# Schematic.net
KiCad netlist of a schematic drawn in Altium Designer
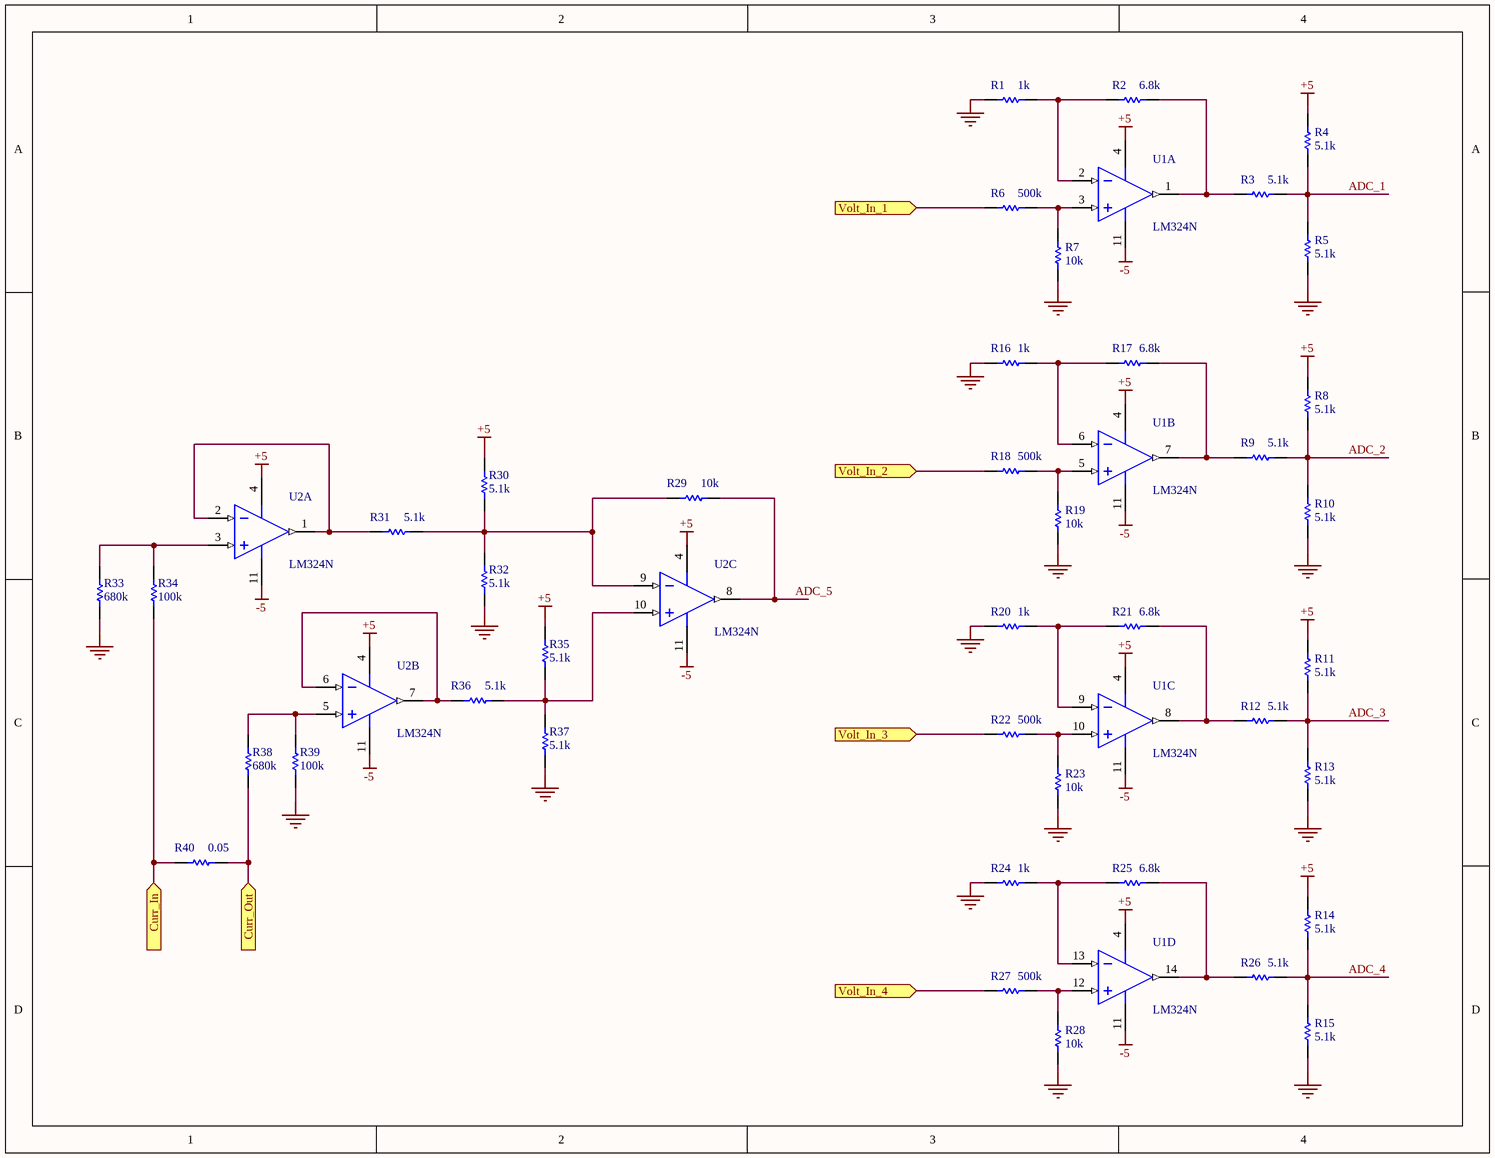
[diagram p0: Schematic.SchDoc]

(export (version "E")
  (design (tool "Eeschema 10.0.6"))
  (components
    (comp (ref "R1")
      (value "1k")
      (footprint "AXIAL-0.3")
      (description "Resistor")
      (fields (field (name "PUBLISHER") "Altium Limited"))
      (libsource (lib "Miscellaneous Devices") (part "Res1"))
    )
    (comp (ref "R2")
      (value "6.8k")
      (footprint "AXIAL-0.3")
      (description "Resistor")
      (fields (field (name "PUBLISHER") "Altium Limited"))
      (libsource (lib "Miscellaneous Devices") (part "Res1"))
    )
    (comp (ref "R3")
      (value "5.1k")
      (footprint "AXIAL-0.3")
      (description "Resistor")
      (fields (field (name "PUBLISHER") "Altium Limited"))
      (libsource (lib "Miscellaneous Devices") (part "Res1"))
    )
    (comp (ref "R4")
      (value "5.1k")
      (footprint "AXIAL-0.3")
      (description "Resistor")
      (fields (field (name "PUBLISHER") "Altium Limited"))
      (libsource (lib "Miscellaneous Devices") (part "Res1"))
    )
    (comp (ref "R5")
      (value "5.1k")
      (footprint "AXIAL-0.3")
      (description "Resistor")
      (fields (field (name "PUBLISHER") "Altium Limited"))
      (libsource (lib "Miscellaneous Devices") (part "Res1"))
    )
    (comp (ref "R6")
      (value "500k")
      (footprint "AXIAL-0.3")
      (description "Resistor")
      (fields (field (name "PUBLISHER") "Altium Limited"))
      (libsource (lib "Miscellaneous Devices") (part "Res1"))
    )
    (comp (ref "R7")
      (value "10k")
      (footprint "AXIAL-0.3")
      (description "Resistor")
      (fields (field (name "PUBLISHER") "Altium Limited"))
      (libsource (lib "Miscellaneous Devices") (part "Res1"))
    )
    (comp (ref "R8")
      (value "5.1k")
      (footprint "AXIAL-0.3")
      (description "Resistor")
      (fields (field (name "PUBLISHER") "Altium Limited"))
      (libsource (lib "Miscellaneous Devices") (part "Res1"))
    )
    (comp (ref "R9")
      (value "5.1k")
      (footprint "AXIAL-0.3")
      (description "Resistor")
      (fields (field (name "PUBLISHER") "Altium Limited"))
      (libsource (lib "Miscellaneous Devices") (part "Res1"))
    )
    (comp (ref "R10")
      (value "5.1k")
      (footprint "AXIAL-0.3")
      (description "Resistor")
      (fields (field (name "PUBLISHER") "Altium Limited"))
      (libsource (lib "Miscellaneous Devices") (part "Res1"))
    )
    (comp (ref "R11")
      (value "5.1k")
      (footprint "AXIAL-0.3")
      (description "Resistor")
      (fields (field (name "PUBLISHER") "Altium Limited"))
      (libsource (lib "Miscellaneous Devices") (part "Res1"))
    )
    (comp (ref "R12")
      (value "5.1k")
      (footprint "AXIAL-0.3")
      (description "Resistor")
      (fields (field (name "PUBLISHER") "Altium Limited"))
      (libsource (lib "Miscellaneous Devices") (part "Res1"))
    )
    (comp (ref "R13")
      (value "5.1k")
      (footprint "AXIAL-0.3")
      (description "Resistor")
      (fields (field (name "PUBLISHER") "Altium Limited"))
      (libsource (lib "Miscellaneous Devices") (part "Res1"))
    )
    (comp (ref "R14")
      (value "5.1k")
      (footprint "AXIAL-0.3")
      (description "Resistor")
      (fields (field (name "PUBLISHER") "Altium Limited"))
      (libsource (lib "Miscellaneous Devices") (part "Res1"))
    )
    (comp (ref "R15")
      (value "5.1k")
      (footprint "AXIAL-0.3")
      (description "Resistor")
      (fields (field (name "PUBLISHER") "Altium Limited"))
      (libsource (lib "Miscellaneous Devices") (part "Res1"))
    )
    (comp (ref "R16")
      (value "1k")
      (footprint "AXIAL-0.3")
      (description "Resistor")
      (fields (field (name "PUBLISHER") "Altium Limited"))
      (libsource (lib "Miscellaneous Devices") (part "Res1"))
    )
    (comp (ref "R17")
      (value "6.8k")
      (footprint "AXIAL-0.3")
      (description "Resistor")
      (fields (field (name "PUBLISHER") "Altium Limited"))
      (libsource (lib "Miscellaneous Devices") (part "Res1"))
    )
    (comp (ref "R18")
      (value "500k")
      (footprint "AXIAL-0.3")
      (description "Resistor")
      (fields (field (name "PUBLISHER") "Altium Limited"))
      (libsource (lib "Miscellaneous Devices") (part "Res1"))
    )
    (comp (ref "R19")
      (value "10k")
      (footprint "AXIAL-0.3")
      (description "Resistor")
      (fields (field (name "PUBLISHER") "Altium Limited"))
      (libsource (lib "Miscellaneous Devices") (part "Res1"))
    )
    (comp (ref "R20")
      (value "1k")
      (footprint "AXIAL-0.3")
      (description "Resistor")
      (fields (field (name "PUBLISHER") "Altium Limited"))
      (libsource (lib "Miscellaneous Devices") (part "Res1"))
    )
    (comp (ref "R21")
      (value "6.8k")
      (footprint "AXIAL-0.3")
      (description "Resistor")
      (fields (field (name "PUBLISHER") "Altium Limited"))
      (libsource (lib "Miscellaneous Devices") (part "Res1"))
    )
    (comp (ref "R22")
      (value "500k")
      (footprint "AXIAL-0.3")
      (description "Resistor")
      (fields (field (name "PUBLISHER") "Altium Limited"))
      (libsource (lib "Miscellaneous Devices") (part "Res1"))
    )
    (comp (ref "R23")
      (value "10k")
      (footprint "AXIAL-0.3")
      (description "Resistor")
      (fields (field (name "PUBLISHER") "Altium Limited"))
      (libsource (lib "Miscellaneous Devices") (part "Res1"))
    )
    (comp (ref "R24")
      (value "1k")
      (footprint "AXIAL-0.3")
      (description "Resistor")
      (fields (field (name "PUBLISHER") "Altium Limited"))
      (libsource (lib "Miscellaneous Devices") (part "Res1"))
    )
    (comp (ref "R25")
      (value "6.8k")
      (footprint "AXIAL-0.3")
      (description "Resistor")
      (fields (field (name "PUBLISHER") "Altium Limited"))
      (libsource (lib "Miscellaneous Devices") (part "Res1"))
    )
    (comp (ref "R26")
      (value "5.1k")
      (footprint "AXIAL-0.3")
      (description "Resistor")
      (fields (field (name "PUBLISHER") "Altium Limited"))
      (libsource (lib "Miscellaneous Devices") (part "Res1"))
    )
    (comp (ref "R27")
      (value "500k")
      (footprint "AXIAL-0.3")
      (description "Resistor")
      (fields (field (name "PUBLISHER") "Altium Limited"))
      (libsource (lib "Miscellaneous Devices") (part "Res1"))
    )
    (comp (ref "R28")
      (value "10k")
      (footprint "AXIAL-0.3")
      (description "Resistor")
      (fields (field (name "PUBLISHER") "Altium Limited"))
      (libsource (lib "Miscellaneous Devices") (part "Res1"))
    )
    (comp (ref "R29")
      (value "10k")
      (footprint "AXIAL-0.3")
      (description "Resistor")
      (fields (field (name "PUBLISHER") "Altium Limited"))
      (libsource (lib "Miscellaneous Devices") (part "Res1"))
    )
    (comp (ref "R30")
      (value "5.1k")
      (footprint "AXIAL-0.3")
      (description "Resistor")
      (fields (field (name "PUBLISHER") "Altium Limited"))
      (libsource (lib "Miscellaneous Devices") (part "Res1"))
    )
    (comp (ref "R31")
      (value "5.1k")
      (footprint "AXIAL-0.3")
      (description "Resistor")
      (fields (field (name "PUBLISHER") "Altium Limited"))
      (libsource (lib "Miscellaneous Devices") (part "Res1"))
    )
    (comp (ref "R32")
      (value "5.1k")
      (footprint "AXIAL-0.3")
      (description "Resistor")
      (fields (field (name "PUBLISHER") "Altium Limited"))
      (libsource (lib "Miscellaneous Devices") (part "Res1"))
    )
    (comp (ref "R33")
      (value "680k")
      (footprint "AXIAL-0.3")
      (description "Resistor")
      (fields (field (name "PUBLISHER") "Altium Limited"))
      (libsource (lib "Miscellaneous Devices") (part "Res1"))
    )
    (comp (ref "R34")
      (value "100k")
      (footprint "AXIAL-0.3")
      (description "Resistor")
      (fields (field (name "PUBLISHER") "Altium Limited"))
      (libsource (lib "Miscellaneous Devices") (part "Res1"))
    )
    (comp (ref "R35")
      (value "5.1k")
      (footprint "AXIAL-0.3")
      (description "Resistor")
      (fields (field (name "PUBLISHER") "Altium Limited"))
      (libsource (lib "Miscellaneous Devices") (part "Res1"))
    )
    (comp (ref "R36")
      (value "5.1k")
      (footprint "AXIAL-0.3")
      (description "Resistor")
      (fields (field (name "PUBLISHER") "Altium Limited"))
      (libsource (lib "Miscellaneous Devices") (part "Res1"))
    )
    (comp (ref "R37")
      (value "5.1k")
      (footprint "AXIAL-0.3")
      (description "Resistor")
      (fields (field (name "PUBLISHER") "Altium Limited"))
      (libsource (lib "Miscellaneous Devices") (part "Res1"))
    )
    (comp (ref "R38")
      (value "680k")
      (footprint "AXIAL-0.3")
      (description "Resistor")
      (fields (field (name "PUBLISHER") "Altium Limited"))
      (libsource (lib "Miscellaneous Devices") (part "Res1"))
    )
    (comp (ref "R39")
      (value "100k")
      (footprint "AXIAL-0.3")
      (description "Resistor")
      (fields (field (name "PUBLISHER") "Altium Limited"))
      (libsource (lib "Miscellaneous Devices") (part "Res1"))
    )
    (comp (ref "R40")
      (value "0.05")
      (footprint "AXIAL-0.3")
      (description "Resistor")
      (fields (field (name "PUBLISHER") "Altium Limited"))
      (libsource (lib "Miscellaneous Devices") (part "Res1"))
    )
    (comp (ref "U1")
      (value "LM324N")
      (footprint "N0014A")
      (description "Low Power Quad Operational Amplifier, 14-pin MDIP")
      (fields (field (name "MANUFACTURER") "Texas Instruments"))
      (libsource (lib "Altium Content Vault") (part "AMP-OPA-LM124-14"))
    )
    (comp (ref "U2")
      (value "LM324N")
      (footprint "N0014A")
      (description "Low Power Quad Operational Amplifier, 14-pin MDIP")
      (fields (field (name "MANUFACTURER") "Texas Instruments"))
      (libsource (lib "Altium Content Vault") (part "AMP-OPA-LM124-14"))
    )
  )
  (nets
    (net (code "1") (name "+5") (class "Default")
      (node (ref "R11") (pin "2") (pinfunction "2_2") (pintype "passive"))
      (node (ref "R14") (pin "2") (pinfunction "2_2") (pintype "passive"))
      (node (ref "R30") (pin "2") (pinfunction "2_2") (pintype "passive"))
      (node (ref "R35") (pin "2") (pinfunction "2_2") (pintype "passive"))
      (node (ref "R4") (pin "2") (pinfunction "2_2") (pintype "passive"))
      (node (ref "R8") (pin "2") (pinfunction "2_2") (pintype "passive"))
      (node (ref "U1") (pin "4") (pinfunction "V+_4") (pintype "power_in"))
      (node (ref "U2") (pin "4") (pinfunction "V+_4") (pintype "power_in"))
    )
    (net (code "2") (name "-5") (class "Default")
      (node (ref "U1") (pin "11") (pinfunction "GND_11") (pintype "power_in"))
      (node (ref "U2") (pin "11") (pinfunction "GND_11") (pintype "power_in"))
    )
    (net (code "3") (name "/ADC_1") (class "Default")
      (node (ref "R3") (pin "2") (pinfunction "2_2") (pintype "passive"))
      (node (ref "R4") (pin "1") (pinfunction "1_1") (pintype "passive"))
      (node (ref "R5") (pin "2") (pinfunction "2_2") (pintype "passive"))
    )
    (net (code "4") (name "/ADC_2") (class "Default")
      (node (ref "R10") (pin "2") (pinfunction "2_2") (pintype "passive"))
      (node (ref "R8") (pin "1") (pinfunction "1_1") (pintype "passive"))
      (node (ref "R9") (pin "2") (pinfunction "2_2") (pintype "passive"))
    )
    (net (code "5") (name "/ADC_3") (class "Default")
      (node (ref "R11") (pin "1") (pinfunction "1_1") (pintype "passive"))
      (node (ref "R12") (pin "2") (pinfunction "2_2") (pintype "passive"))
      (node (ref "R13") (pin "2") (pinfunction "2_2") (pintype "passive"))
    )
    (net (code "6") (name "/ADC_4") (class "Default")
      (node (ref "R14") (pin "1") (pinfunction "1_1") (pintype "passive"))
      (node (ref "R15") (pin "2") (pinfunction "2_2") (pintype "passive"))
      (node (ref "R26") (pin "2") (pinfunction "2_2") (pintype "passive"))
    )
    (net (code "7") (name "/ADC_5") (class "Default")
      (node (ref "R29") (pin "1") (pinfunction "1_1") (pintype "passive"))
      (node (ref "U2") (pin "8") (pinfunction "OUT3_8") (pintype "output"))
    )
    (net (code "8") (name "/Curr_In") (class "Default")
      (node (ref "R34") (pin "1") (pinfunction "1_1") (pintype "passive"))
      (node (ref "R40") (pin "1") (pinfunction "1_1") (pintype "passive"))
    )
    (net (code "9") (name "/Curr_Out") (class "Default")
      (node (ref "R38") (pin "1") (pinfunction "1_1") (pintype "passive"))
      (node (ref "R40") (pin "2") (pinfunction "2_2") (pintype "passive"))
    )
    (net (code "10") (name "/Volt_In_1") (class "Default")
      (node (ref "R6") (pin "1") (pinfunction "1_1") (pintype "passive"))
    )
    (net (code "11") (name "/Volt_In_2") (class "Default")
      (node (ref "R18") (pin "1") (pinfunction "1_1") (pintype "passive"))
    )
    (net (code "12") (name "/Volt_In_3") (class "Default")
      (node (ref "R22") (pin "1") (pinfunction "1_1") (pintype "passive"))
    )
    (net (code "13") (name "/Volt_In_4") (class "Default")
      (node (ref "R27") (pin "1") (pinfunction "1_1") (pintype "passive"))
    )
    (net (code "14") (name "GND") (class "Default")
      (node (ref "R1") (pin "1") (pinfunction "1_1") (pintype "passive"))
      (node (ref "R10") (pin "1") (pinfunction "1_1") (pintype "passive"))
      (node (ref "R13") (pin "1") (pinfunction "1_1") (pintype "passive"))
      (node (ref "R15") (pin "1") (pinfunction "1_1") (pintype "passive"))
      (node (ref "R16") (pin "1") (pinfunction "1_1") (pintype "passive"))
      (node (ref "R19") (pin "1") (pinfunction "1_1") (pintype "passive"))
      (node (ref "R20") (pin "1") (pinfunction "1_1") (pintype "passive"))
      (node (ref "R23") (pin "1") (pinfunction "1_1") (pintype "passive"))
      (node (ref "R24") (pin "1") (pinfunction "1_1") (pintype "passive"))
      (node (ref "R28") (pin "1") (pinfunction "1_1") (pintype "passive"))
      (node (ref "R32") (pin "1") (pinfunction "1_1") (pintype "passive"))
      (node (ref "R33") (pin "1") (pinfunction "1_1") (pintype "passive"))
      (node (ref "R37") (pin "1") (pinfunction "1_1") (pintype "passive"))
      (node (ref "R39") (pin "1") (pinfunction "1_1") (pintype "passive"))
      (node (ref "R5") (pin "1") (pinfunction "1_1") (pintype "passive"))
      (node (ref "R7") (pin "1") (pinfunction "1_1") (pintype "passive"))
    )
    (net (code "15") (name "Net-(U1A-IN1+)") (class "Default")
      (node (ref "R6") (pin "2") (pinfunction "2_2") (pintype "passive"))
      (node (ref "R7") (pin "2") (pinfunction "2_2") (pintype "passive"))
      (node (ref "U1") (pin "3") (pinfunction "IN1+_3") (pintype "input"))
    )
    (net (code "16") (name "Net-(U1A-IN1-)") (class "Default")
      (node (ref "R1") (pin "2") (pinfunction "2_2") (pintype "passive"))
      (node (ref "R2") (pin "1") (pinfunction "1_1") (pintype "passive"))
      (node (ref "U1") (pin "2") (pinfunction "IN1-_2") (pintype "input"))
    )
    (net (code "17") (name "Net-(U1A-OUT1)") (class "Default")
      (node (ref "R2") (pin "2") (pinfunction "2_2") (pintype "passive"))
      (node (ref "R3") (pin "1") (pinfunction "1_1") (pintype "passive"))
      (node (ref "U1") (pin "1") (pinfunction "OUT1_1") (pintype "output"))
    )
    (net (code "18") (name "Net-(U1B-IN2+)") (class "Default")
      (node (ref "R18") (pin "2") (pinfunction "2_2") (pintype "passive"))
      (node (ref "R19") (pin "2") (pinfunction "2_2") (pintype "passive"))
      (node (ref "U1") (pin "5") (pinfunction "IN2+_5") (pintype "input"))
    )
    (net (code "19") (name "Net-(U1B-IN2-)") (class "Default")
      (node (ref "R16") (pin "2") (pinfunction "2_2") (pintype "passive"))
      (node (ref "R17") (pin "1") (pinfunction "1_1") (pintype "passive"))
      (node (ref "U1") (pin "6") (pinfunction "IN2-_6") (pintype "input"))
    )
    (net (code "20") (name "Net-(U1B-OUT2)") (class "Default")
      (node (ref "R17") (pin "2") (pinfunction "2_2") (pintype "passive"))
      (node (ref "R9") (pin "1") (pinfunction "1_1") (pintype "passive"))
      (node (ref "U1") (pin "7") (pinfunction "OUT2_7") (pintype "output"))
    )
    (net (code "21") (name "Net-(U1C-IN3+)") (class "Default")
      (node (ref "R22") (pin "2") (pinfunction "2_2") (pintype "passive"))
      (node (ref "R23") (pin "2") (pinfunction "2_2") (pintype "passive"))
      (node (ref "U1") (pin "10") (pinfunction "IN3+_10") (pintype "input"))
    )
    (net (code "22") (name "Net-(U1C-IN3-)") (class "Default")
      (node (ref "R20") (pin "2") (pinfunction "2_2") (pintype "passive"))
      (node (ref "R21") (pin "1") (pinfunction "1_1") (pintype "passive"))
      (node (ref "U1") (pin "9") (pinfunction "IN3-_9") (pintype "input"))
    )
    (net (code "23") (name "Net-(U1C-OUT3)") (class "Default")
      (node (ref "R12") (pin "1") (pinfunction "1_1") (pintype "passive"))
      (node (ref "R21") (pin "2") (pinfunction "2_2") (pintype "passive"))
      (node (ref "U1") (pin "8") (pinfunction "OUT3_8") (pintype "output"))
    )
    (net (code "24") (name "Net-(U1D-IN4+)") (class "Default")
      (node (ref "R27") (pin "2") (pinfunction "2_2") (pintype "passive"))
      (node (ref "R28") (pin "2") (pinfunction "2_2") (pintype "passive"))
      (node (ref "U1") (pin "12") (pinfunction "IN4+_12") (pintype "input"))
    )
    (net (code "25") (name "Net-(U1D-IN4-)") (class "Default")
      (node (ref "R24") (pin "2") (pinfunction "2_2") (pintype "passive"))
      (node (ref "R25") (pin "1") (pinfunction "1_1") (pintype "passive"))
      (node (ref "U1") (pin "13") (pinfunction "IN4-_13") (pintype "input"))
    )
    (net (code "26") (name "Net-(U1D-OUT4)") (class "Default")
      (node (ref "R25") (pin "2") (pinfunction "2_2") (pintype "passive"))
      (node (ref "R26") (pin "1") (pinfunction "1_1") (pintype "passive"))
      (node (ref "U1") (pin "14") (pinfunction "OUT4_14") (pintype "output"))
    )
    (net (code "27") (name "Net-(U2A-IN1+)") (class "Default")
      (node (ref "R33") (pin "2") (pinfunction "2_2") (pintype "passive"))
      (node (ref "R34") (pin "2") (pinfunction "2_2") (pintype "passive"))
      (node (ref "U2") (pin "3") (pinfunction "IN1+_3") (pintype "input"))
    )
    (net (code "28") (name "Net-(U2A-IN1-)") (class "Default")
      (node (ref "R31") (pin "2") (pinfunction "2_2") (pintype "passive"))
      (node (ref "U2") (pin "1") (pinfunction "OUT1_1") (pintype "output"))
      (node (ref "U2") (pin "2") (pinfunction "IN1-_2") (pintype "input"))
    )
    (net (code "29") (name "Net-(U2B-IN2+)") (class "Default")
      (node (ref "R38") (pin "2") (pinfunction "2_2") (pintype "passive"))
      (node (ref "R39") (pin "2") (pinfunction "2_2") (pintype "passive"))
      (node (ref "U2") (pin "5") (pinfunction "IN2+_5") (pintype "input"))
    )
    (net (code "30") (name "Net-(U2B-IN2-)") (class "Default")
      (node (ref "R36") (pin "2") (pinfunction "2_2") (pintype "passive"))
      (node (ref "U2") (pin "6") (pinfunction "IN2-_6") (pintype "input"))
      (node (ref "U2") (pin "7") (pinfunction "OUT2_7") (pintype "output"))
    )
    (net (code "31") (name "Net-(U2C-IN3+)") (class "Default")
      (node (ref "R35") (pin "1") (pinfunction "1_1") (pintype "passive"))
      (node (ref "R36") (pin "1") (pinfunction "1_1") (pintype "passive"))
      (node (ref "R37") (pin "2") (pinfunction "2_2") (pintype "passive"))
      (node (ref "U2") (pin "10") (pinfunction "IN3+_10") (pintype "input"))
    )
    (net (code "32") (name "Net-(U2C-IN3-)") (class "Default")
      (node (ref "R29") (pin "2") (pinfunction "2_2") (pintype "passive"))
      (node (ref "R30") (pin "1") (pinfunction "1_1") (pintype "passive"))
      (node (ref "R31") (pin "1") (pinfunction "1_1") (pintype "passive"))
      (node (ref "R32") (pin "2") (pinfunction "2_2") (pintype "passive"))
      (node (ref "U2") (pin "9") (pinfunction "IN3-_9") (pintype "input"))
    )
  )
)
